# stm_shild.net
KiCad netlist of a schematic drawn in EAGLE
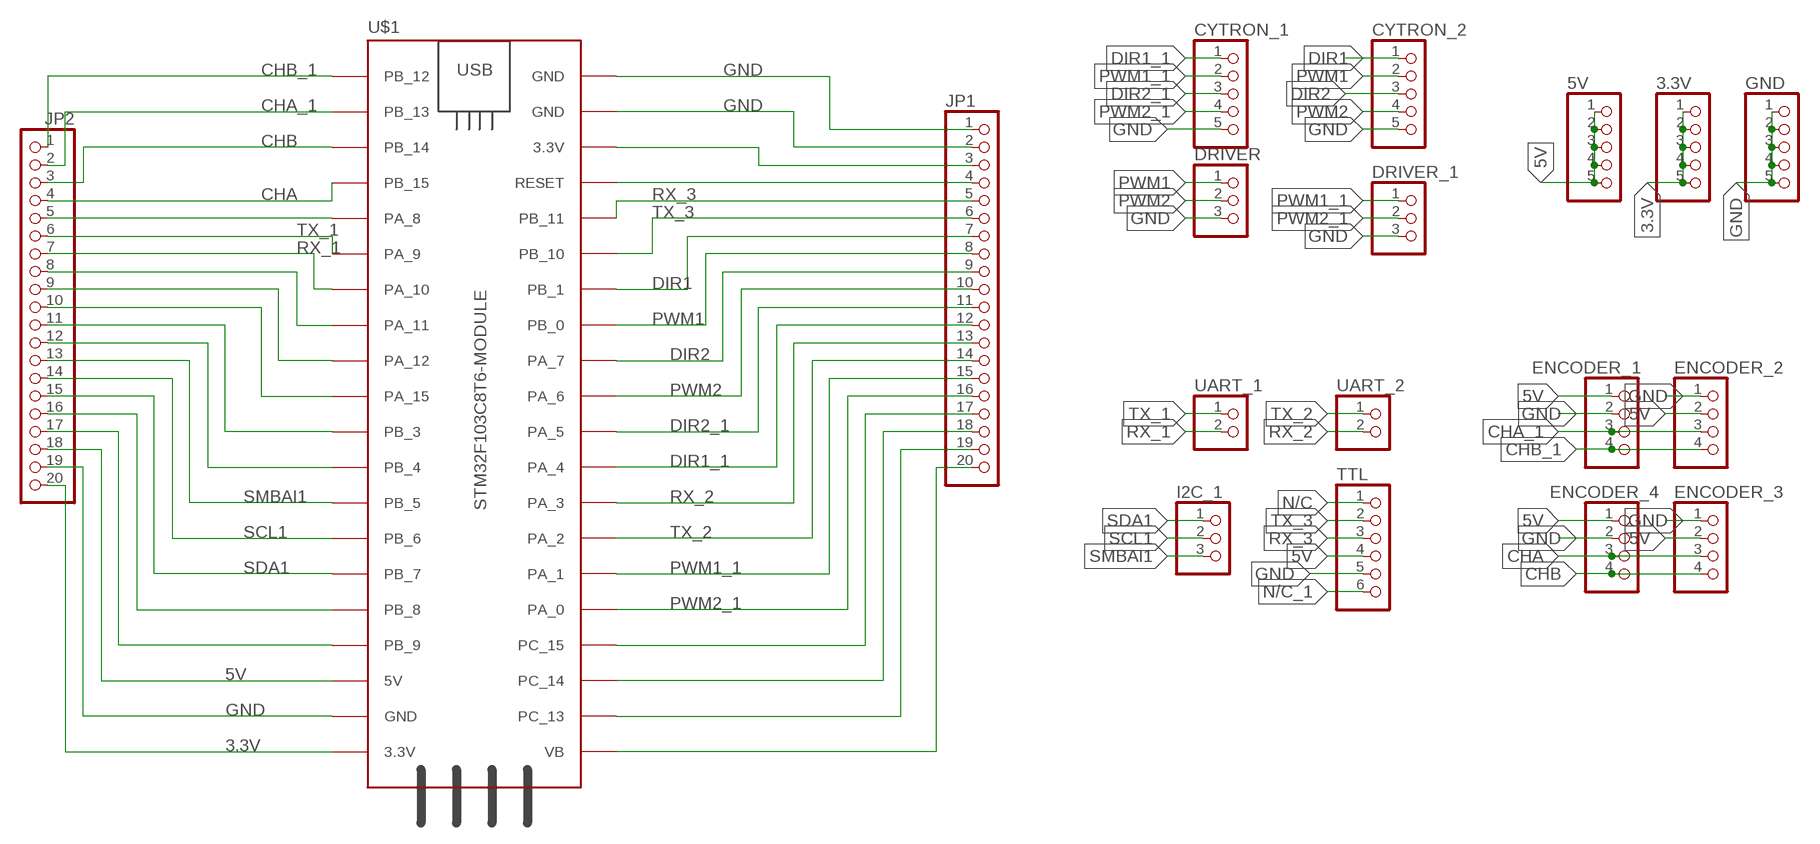
[diagram p0: schematic, sheet 1]

(export (version "E")
  (design (tool "Eeschema 10.0.6"))
  (components
    (comp (ref "3.3V")
      (value "PINHD-1X5")
      (footprint "eagle-import:1X05")
      (libsource (lib "eagle-import") (part "PINHD-1X5"))
    )
    (comp (ref "5V")
      (value "PINHD-1X5")
      (footprint "eagle-import:1X05")
      (libsource (lib "eagle-import") (part "PINHD-1X5"))
    )
    (comp (ref "CYTRON_1")
      (value "PINHD-1X5")
      (footprint "eagle-import:1X05")
      (libsource (lib "eagle-import") (part "PINHD-1X5"))
    )
    (comp (ref "CYTRON_2")
      (value "PINHD-1X5")
      (footprint "eagle-import:1X05")
      (libsource (lib "eagle-import") (part "PINHD-1X5"))
    )
    (comp (ref "DRIVER")
      (value "PINHD-1X3")
      (footprint "eagle-import:1X03")
      (libsource (lib "eagle-import") (part "PINHD-1X3"))
    )
    (comp (ref "DRIVER_1")
      (value "PINHD-1X3")
      (footprint "eagle-import:1X03")
      (libsource (lib "eagle-import") (part "PINHD-1X3"))
    )
    (comp (ref "ENCODER_1")
      (value "PINHD-1X4")
      (footprint "eagle-import:1X04")
      (libsource (lib "eagle-import") (part "PINHD-1X4"))
    )
    (comp (ref "ENCODER_2")
      (value "PINHD-1X4")
      (footprint "eagle-import:1X04")
      (libsource (lib "eagle-import") (part "PINHD-1X4"))
    )
    (comp (ref "ENCODER_3")
      (value "PINHD-1X4")
      (footprint "eagle-import:1X04")
      (libsource (lib "eagle-import") (part "PINHD-1X4"))
    )
    (comp (ref "ENCODER_4")
      (value "PINHD-1X4")
      (footprint "eagle-import:1X04")
      (libsource (lib "eagle-import") (part "PINHD-1X4"))
    )
    (comp (ref "GND")
      (value "PINHD-1X5")
      (footprint "eagle-import:1X05")
      (libsource (lib "eagle-import") (part "PINHD-1X5"))
    )
    (comp (ref "I2C_1")
      (value "PINHD-1X3")
      (footprint "eagle-import:1X03")
      (libsource (lib "eagle-import") (part "PINHD-1X3"))
    )
    (comp (ref "JP1")
      (value "PINHD-1X20")
      (footprint "eagle-import:1X20")
      (libsource (lib "eagle-import") (part "PINHD-1X20"))
    )
    (comp (ref "JP2")
      (value "PINHD-1X20")
      (footprint "eagle-import:1X20")
      (libsource (lib "eagle-import") (part "PINHD-1X20"))
    )
    (comp (ref "TTL")
      (value "PINHD-1X6")
      (footprint "eagle-import:1X06")
      (libsource (lib "eagle-import") (part "PINHD-1X6"))
    )
    (comp (ref "U$1")
      (value "STM32F103C8T6-MODULE")
      (footprint "eagle-import:STM32F103C8T6-MODULE")
      (libsource (lib "eagle-import") (part "STM32F103C8T6-MODULE"))
    )
    (comp (ref "UART_1")
      (value "PINHD-1X2")
      (footprint "eagle-import:1X02")
      (libsource (lib "eagle-import") (part "PINHD-1X2"))
    )
    (comp (ref "UART_2")
      (value "PINHD-1X2")
      (footprint "eagle-import:1X02")
      (libsource (lib "eagle-import") (part "PINHD-1X2"))
    )
  )
  (nets
    (net (code "1") (name "3.3V") (class "Default")
      (node (ref "3.3V") (pin "1") (pinfunction "1_1") (pintype "passive"))
      (node (ref "3.3V") (pin "2") (pinfunction "2_2") (pintype "passive"))
      (node (ref "3.3V") (pin "3") (pinfunction "3_3") (pintype "passive"))
      (node (ref "3.3V") (pin "4") (pinfunction "4_4") (pintype "passive"))
      (node (ref "3.3V") (pin "5") (pinfunction "5_5") (pintype "passive"))
      (node (ref "JP2") (pin "20") (pinfunction "20_20") (pintype "passive"))
      (node (ref "U$1") (pin "3.3V_1") (pinfunction "3.3V_3.3V_1") (pintype "bidirectional"))
    )
    (net (code "2") (name "5V") (class "Default")
      (node (ref "5V") (pin "1") (pinfunction "1_1") (pintype "passive"))
      (node (ref "5V") (pin "2") (pinfunction "2_2") (pintype "passive"))
      (node (ref "5V") (pin "3") (pinfunction "3_3") (pintype "passive"))
      (node (ref "5V") (pin "4") (pinfunction "4_4") (pintype "passive"))
      (node (ref "5V") (pin "5") (pinfunction "5_5") (pintype "passive"))
      (node (ref "ENCODER_1") (pin "1") (pinfunction "1_1") (pintype "passive"))
      (node (ref "ENCODER_2") (pin "2") (pinfunction "2_2") (pintype "passive"))
      (node (ref "ENCODER_3") (pin "2") (pinfunction "2_2") (pintype "passive"))
      (node (ref "ENCODER_4") (pin "1") (pinfunction "1_1") (pintype "passive"))
      (node (ref "JP2") (pin "18") (pinfunction "18_18") (pintype "passive"))
      (node (ref "TTL") (pin "4") (pinfunction "4_4") (pintype "passive"))
      (node (ref "U$1") (pin "5V") (pinfunction "5V_5V") (pintype "bidirectional"))
    )
    (net (code "3") (name "CHA") (class "Default")
      (node (ref "ENCODER_3") (pin "3") (pinfunction "3_3") (pintype "passive"))
      (node (ref "ENCODER_4") (pin "3") (pinfunction "3_3") (pintype "passive"))
      (node (ref "JP2") (pin "4") (pinfunction "4_4") (pintype "passive"))
      (node (ref "U$1") (pin "PB_15") (pinfunction "PB_15_PB_15") (pintype "bidirectional"))
    )
    (net (code "4") (name "CHA_1") (class "Default")
      (node (ref "ENCODER_1") (pin "3") (pinfunction "3_3") (pintype "passive"))
      (node (ref "ENCODER_2") (pin "3") (pinfunction "3_3") (pintype "passive"))
      (node (ref "JP2") (pin "2") (pinfunction "2_2") (pintype "passive"))
      (node (ref "U$1") (pin "PB_13") (pinfunction "PB_13_PB_13") (pintype "bidirectional"))
    )
    (net (code "5") (name "CHB") (class "Default")
      (node (ref "ENCODER_3") (pin "4") (pinfunction "4_4") (pintype "passive"))
      (node (ref "ENCODER_4") (pin "4") (pinfunction "4_4") (pintype "passive"))
      (node (ref "JP2") (pin "3") (pinfunction "3_3") (pintype "passive"))
      (node (ref "U$1") (pin "PB_14") (pinfunction "PB_14_PB_14") (pintype "bidirectional"))
    )
    (net (code "6") (name "CHB_1") (class "Default")
      (node (ref "ENCODER_1") (pin "4") (pinfunction "4_4") (pintype "passive"))
      (node (ref "ENCODER_2") (pin "4") (pinfunction "4_4") (pintype "passive"))
      (node (ref "JP2") (pin "1") (pinfunction "1_1") (pintype "passive"))
      (node (ref "U$1") (pin "PB_12") (pinfunction "PB_12_PB_12") (pintype "bidirectional"))
    )
    (net (code "7") (name "DIR1") (class "Default")
      (node (ref "CYTRON_2") (pin "1") (pinfunction "1_1") (pintype "passive"))
      (node (ref "JP1") (pin "7") (pinfunction "7_7") (pintype "passive"))
      (node (ref "U$1") (pin "PB_1") (pinfunction "PB_1_PB_1") (pintype "bidirectional"))
    )
    (net (code "8") (name "DIR1_1") (class "Default")
      (node (ref "CYTRON_1") (pin "1") (pinfunction "1_1") (pintype "passive"))
      (node (ref "JP1") (pin "12") (pinfunction "12_12") (pintype "passive"))
      (node (ref "U$1") (pin "PA_4") (pinfunction "PA_4_PA_4") (pintype "bidirectional"))
    )
    (net (code "9") (name "DIR2") (class "Default")
      (node (ref "CYTRON_2") (pin "3") (pinfunction "3_3") (pintype "passive"))
      (node (ref "JP1") (pin "9") (pinfunction "9_9") (pintype "passive"))
      (node (ref "U$1") (pin "PA_7") (pinfunction "PA_7_PA_7") (pintype "bidirectional"))
    )
    (net (code "10") (name "DIR2_1") (class "Default")
      (node (ref "CYTRON_1") (pin "3") (pinfunction "3_3") (pintype "passive"))
      (node (ref "JP1") (pin "11") (pinfunction "11_11") (pintype "passive"))
      (node (ref "U$1") (pin "PA_5") (pinfunction "PA_5_PA_5") (pintype "bidirectional"))
    )
    (net (code "11") (name "GND") (class "Default")
      (node (ref "CYTRON_1") (pin "5") (pinfunction "5_5") (pintype "passive"))
      (node (ref "CYTRON_2") (pin "5") (pinfunction "5_5") (pintype "passive"))
      (node (ref "DRIVER") (pin "3") (pinfunction "3_3") (pintype "passive"))
      (node (ref "DRIVER_1") (pin "3") (pinfunction "3_3") (pintype "passive"))
      (node (ref "ENCODER_1") (pin "2") (pinfunction "2_2") (pintype "passive"))
      (node (ref "ENCODER_2") (pin "1") (pinfunction "1_1") (pintype "passive"))
      (node (ref "ENCODER_3") (pin "1") (pinfunction "1_1") (pintype "passive"))
      (node (ref "ENCODER_4") (pin "2") (pinfunction "2_2") (pintype "passive"))
      (node (ref "GND") (pin "1") (pinfunction "1_1") (pintype "passive"))
      (node (ref "GND") (pin "2") (pinfunction "2_2") (pintype "passive"))
      (node (ref "GND") (pin "3") (pinfunction "3_3") (pintype "passive"))
      (node (ref "GND") (pin "4") (pinfunction "4_4") (pintype "passive"))
      (node (ref "GND") (pin "5") (pinfunction "5_5") (pintype "passive"))
      (node (ref "JP1") (pin "1") (pinfunction "1_1") (pintype "passive"))
      (node (ref "JP1") (pin "2") (pinfunction "2_2") (pintype "passive"))
      (node (ref "JP2") (pin "19") (pinfunction "19_19") (pintype "passive"))
      (node (ref "TTL") (pin "5") (pinfunction "5_5") (pintype "passive"))
      (node (ref "U$1") (pin "GND_1") (pinfunction "GND_GND_1") (pintype "bidirectional"))
      (node (ref "U$1") (pin "GND_2") (pinfunction "GND_GND_2") (pintype "bidirectional"))
      (node (ref "U$1") (pin "GND_3") (pinfunction "GND_GND_3") (pintype "power_in"))
    )
    (net (code "12") (name "Net-(JP1-Pad3)") (class "Default")
      (node (ref "JP1") (pin "3") (pinfunction "3_3") (pintype "passive"))
      (node (ref "U$1") (pin "3.3V_2") (pinfunction "3.3V_3.3V_2") (pintype "bidirectional"))
    )
    (net (code "13") (name "Net-(JP1-Pad4)") (class "Default")
      (node (ref "JP1") (pin "4") (pinfunction "4_4") (pintype "passive"))
      (node (ref "U$1") (pin "RESET") (pinfunction "RESET_RESET") (pintype "bidirectional"))
    )
    (net (code "14") (name "Net-(JP1-Pad17)") (class "Default")
      (node (ref "JP1") (pin "17") (pinfunction "17_17") (pintype "passive"))
      (node (ref "U$1") (pin "PC_15") (pinfunction "PC_15_PC_15") (pintype "bidirectional"))
    )
    (net (code "15") (name "Net-(JP1-Pad18)") (class "Default")
      (node (ref "JP1") (pin "18") (pinfunction "18_18") (pintype "passive"))
      (node (ref "U$1") (pin "PC_14") (pinfunction "PC_14_PC_14") (pintype "bidirectional"))
    )
    (net (code "16") (name "Net-(JP1-Pad19)") (class "Default")
      (node (ref "JP1") (pin "19") (pinfunction "19_19") (pintype "passive"))
      (node (ref "U$1") (pin "PC_13") (pinfunction "PC_13_PC_13") (pintype "bidirectional"))
    )
    (net (code "17") (name "Net-(JP1-Pad20)") (class "Default")
      (node (ref "JP1") (pin "20") (pinfunction "20_20") (pintype "passive"))
      (node (ref "U$1") (pin "VB") (pinfunction "VB_VB") (pintype "bidirectional"))
    )
    (net (code "18") (name "Net-(JP2-Pad5)") (class "Default")
      (node (ref "JP2") (pin "5") (pinfunction "5_5") (pintype "passive"))
      (node (ref "U$1") (pin "PA_8") (pinfunction "PA_8_PA_8") (pintype "bidirectional"))
    )
    (net (code "19") (name "Net-(JP2-Pad8)") (class "Default")
      (node (ref "JP2") (pin "8") (pinfunction "8_8") (pintype "passive"))
      (node (ref "U$1") (pin "PA_11") (pinfunction "PA_11_PA_11") (pintype "bidirectional"))
    )
    (net (code "20") (name "Net-(JP2-Pad9)") (class "Default")
      (node (ref "JP2") (pin "9") (pinfunction "9_9") (pintype "passive"))
      (node (ref "U$1") (pin "PA_12") (pinfunction "PA_12_PA_12") (pintype "bidirectional"))
    )
    (net (code "21") (name "Net-(JP2-Pad10)") (class "Default")
      (node (ref "JP2") (pin "10") (pinfunction "10_10") (pintype "passive"))
      (node (ref "U$1") (pin "PA_15") (pinfunction "PA_15_PA_15") (pintype "bidirectional"))
    )
    (net (code "22") (name "Net-(JP2-Pad11)") (class "Default")
      (node (ref "JP2") (pin "11") (pinfunction "11_11") (pintype "passive"))
      (node (ref "U$1") (pin "PB_3") (pinfunction "PB_3_PB_3") (pintype "bidirectional"))
    )
    (net (code "23") (name "Net-(JP2-Pad12)") (class "Default")
      (node (ref "JP2") (pin "12") (pinfunction "12_12") (pintype "passive"))
      (node (ref "U$1") (pin "PB_4") (pinfunction "PB_4_PB_4") (pintype "bidirectional"))
    )
    (net (code "24") (name "Net-(JP2-Pad16)") (class "Default")
      (node (ref "JP2") (pin "16") (pinfunction "16_16") (pintype "passive"))
      (node (ref "U$1") (pin "PB_8") (pinfunction "PB_8_PB_8") (pintype "bidirectional"))
    )
    (net (code "25") (name "Net-(JP2-Pad17)") (class "Default")
      (node (ref "JP2") (pin "17") (pinfunction "17_17") (pintype "passive"))
      (node (ref "U$1") (pin "PB_9") (pinfunction "PB_9_PB_9") (pintype "bidirectional"))
    )
    (net (code "26") (name "N{slash}C") (class "Default")
      (node (ref "TTL") (pin "1") (pinfunction "1_1") (pintype "passive"))
    )
    (net (code "27") (name "N{slash}C_1") (class "Default")
      (node (ref "TTL") (pin "6") (pinfunction "6_6") (pintype "passive"))
    )
    (net (code "28") (name "PWM1") (class "Default")
      (node (ref "CYTRON_2") (pin "2") (pinfunction "2_2") (pintype "passive"))
      (node (ref "DRIVER") (pin "1") (pinfunction "1_1") (pintype "passive"))
      (node (ref "JP1") (pin "8") (pinfunction "8_8") (pintype "passive"))
      (node (ref "U$1") (pin "PB_0") (pinfunction "PB_0_PB_0") (pintype "bidirectional"))
    )
    (net (code "29") (name "PWM1_1") (class "Default")
      (node (ref "CYTRON_1") (pin "2") (pinfunction "2_2") (pintype "passive"))
      (node (ref "DRIVER_1") (pin "1") (pinfunction "1_1") (pintype "passive"))
      (node (ref "JP1") (pin "15") (pinfunction "15_15") (pintype "passive"))
      (node (ref "U$1") (pin "PA_1") (pinfunction "PA_1_PA_1") (pintype "bidirectional"))
    )
    (net (code "30") (name "PWM2") (class "Default")
      (node (ref "CYTRON_2") (pin "4") (pinfunction "4_4") (pintype "passive"))
      (node (ref "DRIVER") (pin "2") (pinfunction "2_2") (pintype "passive"))
      (node (ref "JP1") (pin "10") (pinfunction "10_10") (pintype "passive"))
      (node (ref "U$1") (pin "PA_6") (pinfunction "PA_6_PA_6") (pintype "bidirectional"))
    )
    (net (code "31") (name "PWM2_1") (class "Default")
      (node (ref "CYTRON_1") (pin "4") (pinfunction "4_4") (pintype "passive"))
      (node (ref "DRIVER_1") (pin "2") (pinfunction "2_2") (pintype "passive"))
      (node (ref "JP1") (pin "16") (pinfunction "16_16") (pintype "passive"))
      (node (ref "U$1") (pin "PA_0") (pinfunction "PA_0_PA_0") (pintype "bidirectional"))
    )
    (net (code "32") (name "RX_1") (class "Default")
      (node (ref "JP2") (pin "7") (pinfunction "7_7") (pintype "passive"))
      (node (ref "U$1") (pin "PA_10") (pinfunction "PA_10_PA_10") (pintype "bidirectional"))
      (node (ref "UART_1") (pin "2") (pinfunction "2_2") (pintype "passive"))
    )
    (net (code "33") (name "RX_2") (class "Default")
      (node (ref "JP1") (pin "13") (pinfunction "13_13") (pintype "passive"))
      (node (ref "U$1") (pin "PA_3") (pinfunction "PA_3_PA_3") (pintype "bidirectional"))
      (node (ref "UART_2") (pin "2") (pinfunction "2_2") (pintype "passive"))
    )
    (net (code "34") (name "RX_3") (class "Default")
      (node (ref "JP1") (pin "5") (pinfunction "5_5") (pintype "passive"))
      (node (ref "TTL") (pin "3") (pinfunction "3_3") (pintype "passive"))
      (node (ref "U$1") (pin "PB_11") (pinfunction "PB_11_PB_11") (pintype "bidirectional"))
    )
    (net (code "35") (name "SCL1") (class "Default")
      (node (ref "I2C_1") (pin "2") (pinfunction "2_2") (pintype "passive"))
      (node (ref "JP2") (pin "14") (pinfunction "14_14") (pintype "passive"))
      (node (ref "U$1") (pin "PB_6") (pinfunction "PB_6_PB_6") (pintype "bidirectional"))
    )
    (net (code "36") (name "SDA1") (class "Default")
      (node (ref "I2C_1") (pin "1") (pinfunction "1_1") (pintype "passive"))
      (node (ref "JP2") (pin "15") (pinfunction "15_15") (pintype "passive"))
      (node (ref "U$1") (pin "PB_7") (pinfunction "PB_7_PB_7") (pintype "bidirectional"))
    )
    (net (code "37") (name "SMBAI1") (class "Default")
      (node (ref "I2C_1") (pin "3") (pinfunction "3_3") (pintype "passive"))
      (node (ref "JP2") (pin "13") (pinfunction "13_13") (pintype "passive"))
      (node (ref "U$1") (pin "PB_5") (pinfunction "PB_5_PB_5") (pintype "bidirectional"))
    )
    (net (code "38") (name "TX_1") (class "Default")
      (node (ref "JP2") (pin "6") (pinfunction "6_6") (pintype "passive"))
      (node (ref "U$1") (pin "PA_9") (pinfunction "PA_9_PA_9") (pintype "bidirectional"))
      (node (ref "UART_1") (pin "1") (pinfunction "1_1") (pintype "passive"))
    )
    (net (code "39") (name "TX_2") (class "Default")
      (node (ref "JP1") (pin "14") (pinfunction "14_14") (pintype "passive"))
      (node (ref "U$1") (pin "PA_2") (pinfunction "PA_2_PA_2") (pintype "bidirectional"))
      (node (ref "UART_2") (pin "1") (pinfunction "1_1") (pintype "passive"))
    )
    (net (code "40") (name "TX_3") (class "Default")
      (node (ref "JP1") (pin "6") (pinfunction "6_6") (pintype "passive"))
      (node (ref "TTL") (pin "2") (pinfunction "2_2") (pintype "passive"))
      (node (ref "U$1") (pin "PB_10") (pinfunction "PB_10_PB_10") (pintype "bidirectional"))
    )
  )
)
